# TinyRulerPE.net
KiCad netlist of a schematic drawn in EAGLE
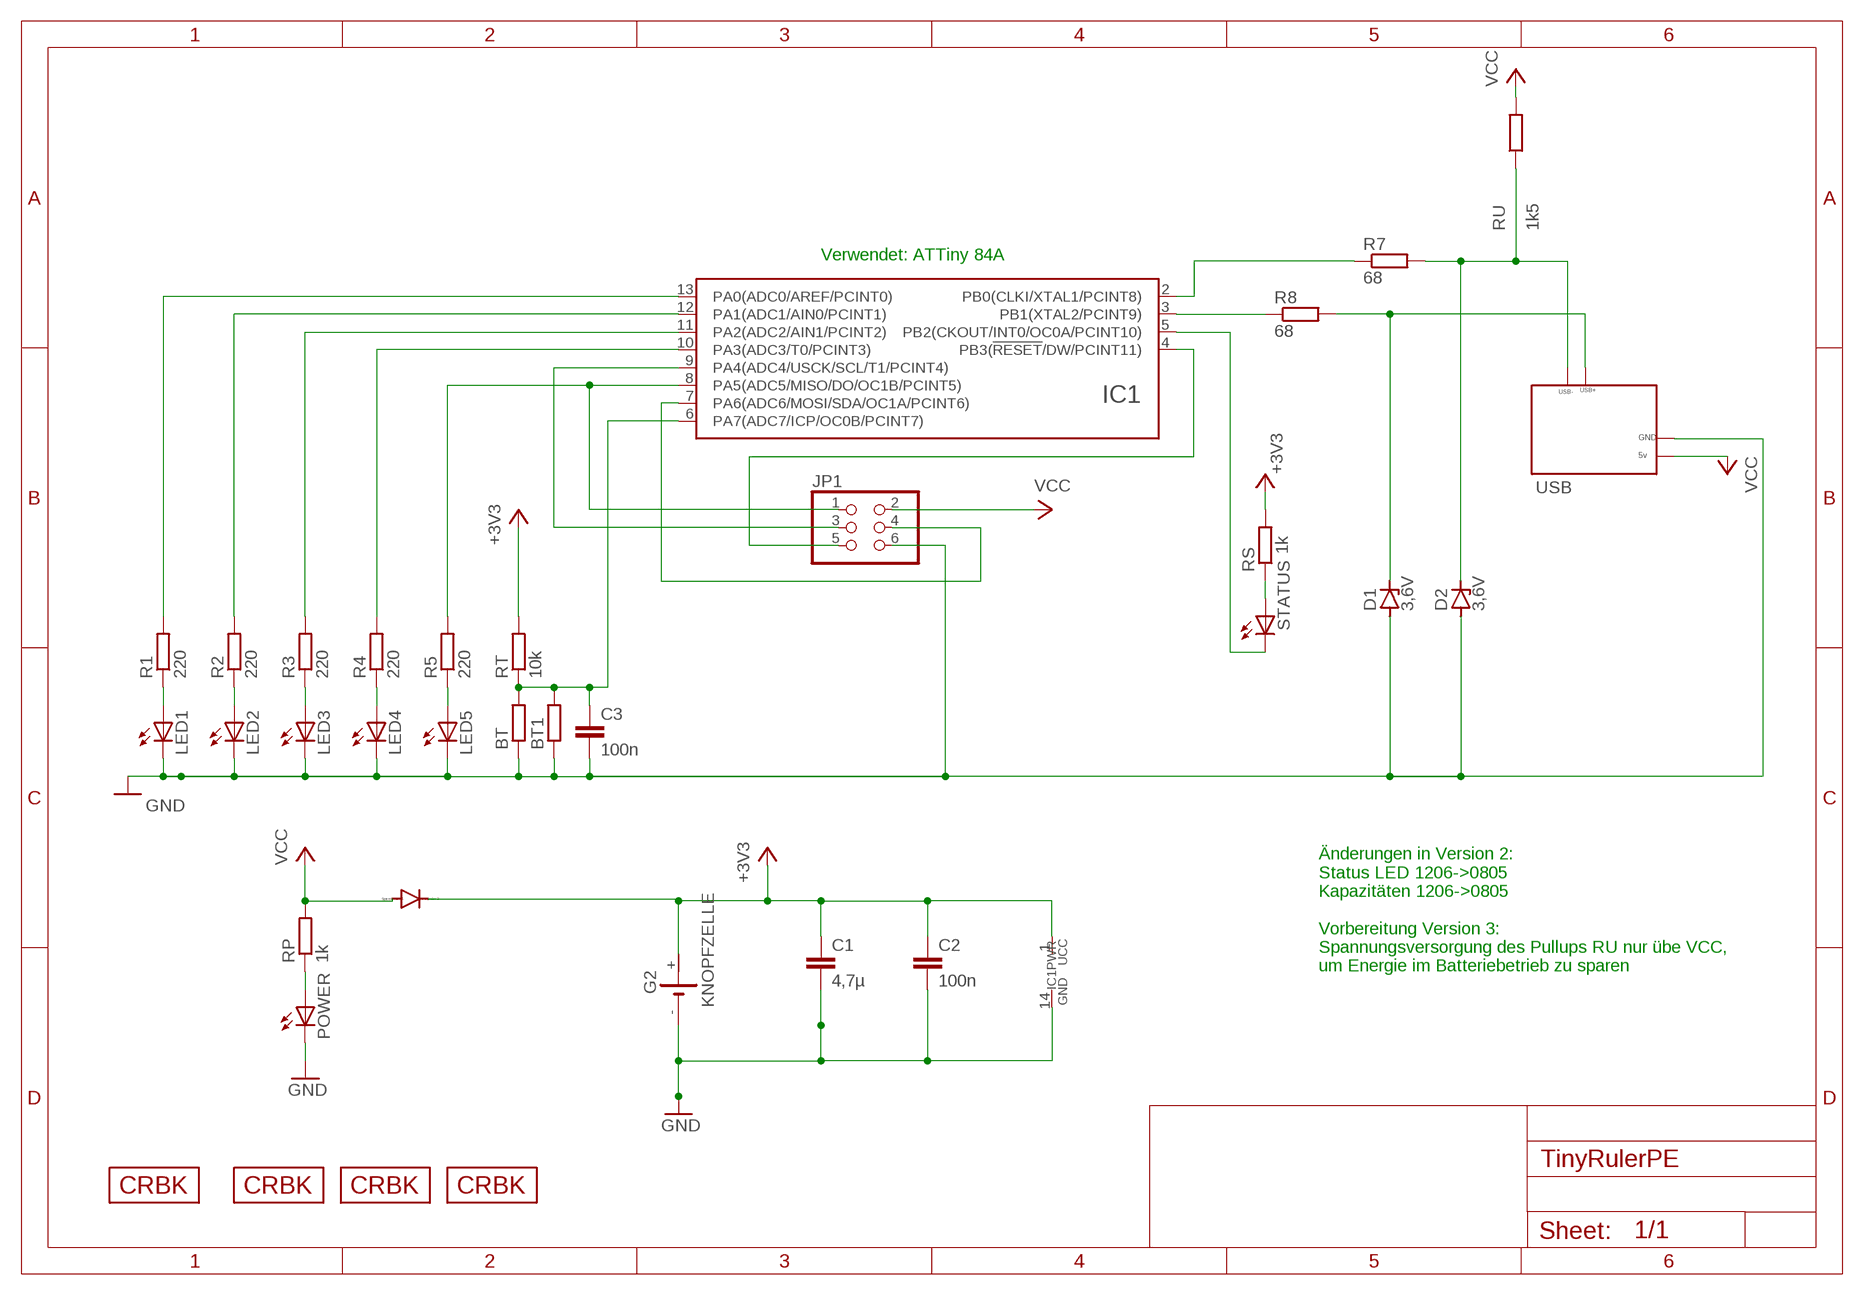
[diagram p0: schematic, sheet 1]

(export (version "E")
  (design (tool "Eeschema 10.0.6"))
  (components
    (comp (ref "BT")
      (value "R-EU_0411/15")
      (footprint "eagle-import:0411_15")
      (libsource (lib "eagle-import") (part "R-EU_0411/15"))
    )
    (comp (ref "BT1")
      (value "R-EU_0309/10")
      (footprint "eagle-import:0309_10")
      (libsource (lib "eagle-import") (part "R-EU_0309/10"))
    )
    (comp (ref "C1")
      (value "4,7µ")
      (footprint "eagle-import:C0805")
      (libsource (lib "eagle-import") (part "C-EUC0805"))
    )
    (comp (ref "C2")
      (value "100n")
      (footprint "eagle-import:C0805")
      (libsource (lib "eagle-import") (part "C-EUC0805"))
    )
    (comp (ref "C3")
      (value "100n")
      (footprint "eagle-import:C0805")
      (libsource (lib "eagle-import") (part "C-EUC0805"))
    )
    (comp (ref "D1")
      (value "3,6V")
      (footprint "eagle-import:SOT23")
      (libsource (lib "eagle-import") (part "ZENER-DIODESOT23"))
    )
    (comp (ref "D2")
      (value "3,6V")
      (footprint "eagle-import:SOT23")
      (libsource (lib "eagle-import") (part "ZENER-DIODESOT23"))
    )
    (comp (ref "D4")
      (value "DIODE-SOD323-W")
      (footprint "eagle-import:SOD323-W")
      (libsource (lib "eagle-import") (part "DIODE-SOD323-W"))
    )
    (comp (ref "G2")
      (value "KNOPFZELLE")
      (footprint "eagle-import:KZH20")
      (libsource (lib "eagle-import") (part "KNOPFZELLE"))
    )
    (comp (ref "IC1")
      (value "ATTINY24/44/84-SSU")
      (footprint "eagle-import:SOIC14")
      (libsource (lib "eagle-import") (part "ATTINY24/44/84-SSU"))
    )
    (comp (ref "JP1")
      (value "PINHD-2X3")
      (footprint "eagle-import:2X03")
      (libsource (lib "eagle-import") (part "PINHD-2X3"))
    )
    (comp (ref "L1")
      (value "CRBKLOGO-2020TN_TEXT")
      (footprint "eagle-import:CRBK-LOGO-2020-XS-TN-TEXT")
      (libsource (lib "eagle-import") (part "CRBKLOGO-2020TN_TEXT"))
    )
    (comp (ref "L2")
      (value "CRBKLOGO-2020TN_S_BILD")
      (footprint "eagle-import:CRBK-LOGO-2020-S-TN-BILD")
      (libsource (lib "eagle-import") (part "CRBKLOGO-2020TN_S_BILD"))
    )
    (comp (ref "L3")
      (value "CRBKLOGO-2020TN_S_BILD")
      (footprint "eagle-import:CRBK-LOGO-2020-S-TN-BILD")
      (libsource (lib "eagle-import") (part "CRBKLOGO-2020TN_S_BILD"))
    )
    (comp (ref "L4")
      (value "CRBKLOGO-2020TN_TEXT")
      (footprint "eagle-import:CRBK-LOGO-2020-XS-TN-TEXT")
      (libsource (lib "eagle-import") (part "CRBKLOGO-2020TN_TEXT"))
    )
    (comp (ref "LED1")
      (value "LEDCHIPLED_1206")
      (footprint "eagle-import:CHIPLED_1206")
      (libsource (lib "eagle-import") (part "LEDCHIPLED_1206"))
    )
    (comp (ref "LED2")
      (value "LEDCHIPLED_1206")
      (footprint "eagle-import:CHIPLED_1206")
      (libsource (lib "eagle-import") (part "LEDCHIPLED_1206"))
    )
    (comp (ref "LED3")
      (value "LEDCHIPLED_1206")
      (footprint "eagle-import:CHIPLED_1206")
      (libsource (lib "eagle-import") (part "LEDCHIPLED_1206"))
    )
    (comp (ref "LED4")
      (value "LEDCHIPLED_1206")
      (footprint "eagle-import:CHIPLED_1206")
      (libsource (lib "eagle-import") (part "LEDCHIPLED_1206"))
    )
    (comp (ref "LED5")
      (value "LEDCHIPLED_1206")
      (footprint "eagle-import:CHIPLED_1206")
      (libsource (lib "eagle-import") (part "LEDCHIPLED_1206"))
    )
    (comp (ref "POWER")
      (value "LEDCHIPLED_0805")
      (footprint "eagle-import:CHIPLED_0805")
      (libsource (lib "eagle-import") (part "LEDCHIPLED_0805"))
    )
    (comp (ref "R1")
      (value "220")
      (footprint "eagle-import:R0805")
      (libsource (lib "eagle-import") (part "R-EU_R0805"))
    )
    (comp (ref "R2")
      (value "220")
      (footprint "eagle-import:R0805")
      (libsource (lib "eagle-import") (part "R-EU_R0805"))
    )
    (comp (ref "R3")
      (value "220")
      (footprint "eagle-import:R0805")
      (libsource (lib "eagle-import") (part "R-EU_R0805"))
    )
    (comp (ref "R4")
      (value "220")
      (footprint "eagle-import:R0805")
      (libsource (lib "eagle-import") (part "R-EU_R0805"))
    )
    (comp (ref "R5")
      (value "220")
      (footprint "eagle-import:R0805")
      (libsource (lib "eagle-import") (part "R-EU_R0805"))
    )
    (comp (ref "R7")
      (value "68")
      (footprint "eagle-import:R0805")
      (libsource (lib "eagle-import") (part "R-EU_R0805"))
    )
    (comp (ref "R8")
      (value "68")
      (footprint "eagle-import:R0805")
      (libsource (lib "eagle-import") (part "R-EU_R0805"))
    )
    (comp (ref "RP")
      (value "1k")
      (footprint "eagle-import:R0805")
      (libsource (lib "eagle-import") (part "R-EU_R0805"))
    )
    (comp (ref "RS")
      (value "1k")
      (footprint "eagle-import:R0805")
      (libsource (lib "eagle-import") (part "R-EU_R0805"))
    )
    (comp (ref "RT")
      (value "10k")
      (footprint "eagle-import:R0805")
      (libsource (lib "eagle-import") (part "R-EU_R0805"))
    )
    (comp (ref "RU")
      (value "1k5")
      (footprint "eagle-import:R0805")
      (libsource (lib "eagle-import") (part "R-EU_R0805"))
    )
    (comp (ref "STATUS")
      (value "LEDCHIPLED_0805")
      (footprint "eagle-import:CHIPLED_0805")
      (libsource (lib "eagle-import") (part "LEDCHIPLED_0805"))
    )
    (comp (ref "USB")
      (value "USBCONNECTOR")
      (footprint "eagle-import:USBCONNECTOR")
      (libsource (lib "eagle-import") (part "USBCONNECTOR"))
    )
  )
  (nets
    (net (code "1") (name "+3V3") (class "Default")
      (node (ref "C1") (pin "1") (pinfunction "1_1") (pintype "passive"))
      (node (ref "C2") (pin "1") (pinfunction "1_1") (pintype "passive"))
      (node (ref "D4") (pin "C") (pinfunction "C_C") (pintype "passive"))
      (node (ref "G2") (pin "+") (pinfunction "+_+") (pintype "passive"))
      (node (ref "IC1") (pin "1") (pinfunction "UCC_1") (pintype "power_in"))
      (node (ref "RS") (pin "2") (pinfunction "2_2") (pintype "passive"))
      (node (ref "RT") (pin "2") (pinfunction "2_2") (pintype "passive"))
    )
    (net (code "2") (name "GND") (class "Default")
      (node (ref "BT") (pin "1") (pinfunction "1_1") (pintype "passive"))
      (node (ref "BT1") (pin "1") (pinfunction "1_1") (pintype "passive"))
      (node (ref "C1") (pin "2") (pinfunction "2_2") (pintype "passive"))
      (node (ref "C2") (pin "2") (pinfunction "2_2") (pintype "passive"))
      (node (ref "C3") (pin "2") (pinfunction "2_2") (pintype "passive"))
      (node (ref "D1") (pin "1") (pinfunction "A_1") (pintype "passive"))
      (node (ref "D2") (pin "1") (pinfunction "A_1") (pintype "passive"))
      (node (ref "G2") (pin "-") (pinfunction "-_-") (pintype "passive"))
      (node (ref "IC1") (pin "14") (pinfunction "GND_14") (pintype "power_in"))
      (node (ref "JP1") (pin "6") (pinfunction "6_6") (pintype "passive"))
      (node (ref "LED1") (pin "C") (pinfunction "C_C") (pintype "passive"))
      (node (ref "LED2") (pin "C") (pinfunction "C_C") (pintype "passive"))
      (node (ref "LED3") (pin "C") (pinfunction "C_C") (pintype "passive"))
      (node (ref "LED4") (pin "C") (pinfunction "C_C") (pintype "passive"))
      (node (ref "LED5") (pin "C") (pinfunction "C_C") (pintype "passive"))
      (node (ref "POWER") (pin "C") (pinfunction "C_C") (pintype "passive"))
      (node (ref "USB") (pin "GND") (pinfunction "GND_GND") (pintype "power_in"))
    )
    (net (code "3") (name "Net-(D1-C)") (class "Default")
      (node (ref "D1") (pin "3") (pinfunction "C_3") (pintype "passive"))
      (node (ref "R8") (pin "2") (pinfunction "2_2") (pintype "passive"))
      (node (ref "USB") (pin "USB+") (pinfunction "USB+_USB+") (pintype "bidirectional"))
    )
    (net (code "4") (name "Net-(D2-C)") (class "Default")
      (node (ref "D2") (pin "3") (pinfunction "C_3") (pintype "passive"))
      (node (ref "R7") (pin "2") (pinfunction "2_2") (pintype "passive"))
      (node (ref "RU") (pin "1") (pinfunction "1_1") (pintype "passive"))
      (node (ref "USB") (pin "USB-") (pinfunction "USB-_USB-") (pintype "bidirectional"))
    )
    (net (code "5") (name "Net-(IC1A-PA0(ADC0{slash}AREF{slash}PCINT0))") (class "Default")
      (node (ref "IC1") (pin "13") (pinfunction "PA0(ADC0/AREF/PCINT0)_13") (pintype "bidirectional"))
      (node (ref "R1") (pin "2") (pinfunction "2_2") (pintype "passive"))
    )
    (net (code "6") (name "Net-(IC1A-PA1(ADC1{slash}AIN0{slash}PCINT1))") (class "Default")
      (node (ref "IC1") (pin "12") (pinfunction "PA1(ADC1/AIN0/PCINT1)_12") (pintype "bidirectional"))
      (node (ref "R2") (pin "2") (pinfunction "2_2") (pintype "passive"))
    )
    (net (code "7") (name "Net-(IC1A-PA2(ADC2{slash}AIN1{slash}PCINT2))") (class "Default")
      (node (ref "IC1") (pin "11") (pinfunction "PA2(ADC2/AIN1/PCINT2)_11") (pintype "bidirectional"))
      (node (ref "R3") (pin "2") (pinfunction "2_2") (pintype "passive"))
    )
    (net (code "8") (name "Net-(IC1A-PA3(ADC3{slash}T0{slash}PCINT3))") (class "Default")
      (node (ref "IC1") (pin "10") (pinfunction "PA3(ADC3/T0/PCINT3)_10") (pintype "bidirectional"))
      (node (ref "R4") (pin "2") (pinfunction "2_2") (pintype "passive"))
    )
    (net (code "9") (name "Net-(IC1A-PA4(ADC4{slash}USCK{slash}SCL{slash}T1{slash}PCINT4))") (class "Default")
      (node (ref "IC1") (pin "9") (pinfunction "PA4(ADC4/USCK/SCL/T1/PCINT4)_9") (pintype "bidirectional"))
      (node (ref "JP1") (pin "3") (pinfunction "3_3") (pintype "passive"))
    )
    (net (code "10") (name "Net-(IC1A-PA5(ADC5{slash}MISO{slash}DO{slash}OC1B{slash}PCINT5))") (class "Default")
      (node (ref "IC1") (pin "8") (pinfunction "PA5(ADC5/MISO/DO/OC1B/PCINT5)_8") (pintype "bidirectional"))
      (node (ref "JP1") (pin "1") (pinfunction "1_1") (pintype "passive"))
      (node (ref "R5") (pin "2") (pinfunction "2_2") (pintype "passive"))
    )
    (net (code "11") (name "Net-(IC1A-PA6(ADC6{slash}MOSI{slash}SDA{slash}OC1A{slash}PCINT6))") (class "Default")
      (node (ref "IC1") (pin "7") (pinfunction "PA6(ADC6/MOSI/SDA/OC1A/PCINT6)_7") (pintype "bidirectional"))
      (node (ref "JP1") (pin "4") (pinfunction "4_4") (pintype "passive"))
    )
    (net (code "12") (name "Net-(IC1A-PA7(ADC7{slash}ICP{slash}OC0B{slash}PCINT7))") (class "Default")
      (node (ref "BT") (pin "2") (pinfunction "2_2") (pintype "passive"))
      (node (ref "BT1") (pin "2") (pinfunction "2_2") (pintype "passive"))
      (node (ref "C3") (pin "1") (pinfunction "1_1") (pintype "passive"))
      (node (ref "IC1") (pin "6") (pinfunction "PA7(ADC7/ICP/OC0B/PCINT7)_6") (pintype "bidirectional"))
      (node (ref "RT") (pin "1") (pinfunction "1_1") (pintype "passive"))
    )
    (net (code "13") (name "Net-(IC1A-PB0(CLKI{slash}XTAL1{slash}PCINT8))") (class "Default")
      (node (ref "IC1") (pin "2") (pinfunction "PB0(CLKI/XTAL1/PCINT8)_2") (pintype "bidirectional"))
      (node (ref "R7") (pin "1") (pinfunction "1_1") (pintype "passive"))
    )
    (net (code "14") (name "Net-(IC1A-PB1(XTAL2{slash}PCINT9))") (class "Default")
      (node (ref "IC1") (pin "3") (pinfunction "PB1(XTAL2/PCINT9)_3") (pintype "bidirectional"))
      (node (ref "R8") (pin "1") (pinfunction "1_1") (pintype "passive"))
    )
    (net (code "15") (name "Net-(IC1A-PB2(CKOUT{slash}INT0{slash}OC0A{slash}PCINT10))") (class "Default")
      (node (ref "IC1") (pin "5") (pinfunction "PB2(CKOUT/INT0/OC0A/PCINT10)_5") (pintype "bidirectional"))
      (node (ref "STATUS") (pin "C") (pinfunction "C_C") (pintype "passive"))
    )
    (net (code "16") (name "Net-(IC1A-PB3(~{RESET}{slash}DW{slash}PCINT11))") (class "Default")
      (node (ref "IC1") (pin "4") (pinfunction "PB3(~{RESET}/DW/PCINT11)_4") (pintype "bidirectional"))
      (node (ref "JP1") (pin "5") (pinfunction "5_5") (pintype "passive"))
    )
    (net (code "17") (name "Net-(LED1-PadA)") (class "Default")
      (node (ref "LED1") (pin "A") (pinfunction "A_A") (pintype "passive"))
      (node (ref "R1") (pin "1") (pinfunction "1_1") (pintype "passive"))
    )
    (net (code "18") (name "Net-(LED2-PadA)") (class "Default")
      (node (ref "LED2") (pin "A") (pinfunction "A_A") (pintype "passive"))
      (node (ref "R2") (pin "1") (pinfunction "1_1") (pintype "passive"))
    )
    (net (code "19") (name "Net-(LED3-PadA)") (class "Default")
      (node (ref "LED3") (pin "A") (pinfunction "A_A") (pintype "passive"))
      (node (ref "R3") (pin "1") (pinfunction "1_1") (pintype "passive"))
    )
    (net (code "20") (name "Net-(LED4-PadA)") (class "Default")
      (node (ref "LED4") (pin "A") (pinfunction "A_A") (pintype "passive"))
      (node (ref "R4") (pin "1") (pinfunction "1_1") (pintype "passive"))
    )
    (net (code "21") (name "Net-(LED5-PadA)") (class "Default")
      (node (ref "LED5") (pin "A") (pinfunction "A_A") (pintype "passive"))
      (node (ref "R5") (pin "1") (pinfunction "1_1") (pintype "passive"))
    )
    (net (code "22") (name "Net-(POWER-PadA)") (class "Default")
      (node (ref "POWER") (pin "A") (pinfunction "A_A") (pintype "passive"))
      (node (ref "RP") (pin "1") (pinfunction "1_1") (pintype "passive"))
    )
    (net (code "23") (name "Net-(RS-Pad1)") (class "Default")
      (node (ref "RS") (pin "1") (pinfunction "1_1") (pintype "passive"))
      (node (ref "STATUS") (pin "A") (pinfunction "A_A") (pintype "passive"))
    )
    (net (code "24") (name "VCC") (class "Default")
      (node (ref "D4") (pin "A") (pinfunction "A_A") (pintype "passive"))
      (node (ref "JP1") (pin "2") (pinfunction "2_2") (pintype "passive"))
      (node (ref "RP") (pin "2") (pinfunction "2_2") (pintype "passive"))
      (node (ref "RU") (pin "2") (pinfunction "2_2") (pintype "passive"))
      (node (ref "USB") (pin "+5V") (pinfunction "5V_+5V") (pintype "power_in"))
    )
  )
)
